# IDX_CTRL.net
KiCad netlist of a schematic drawn in Altium Designer
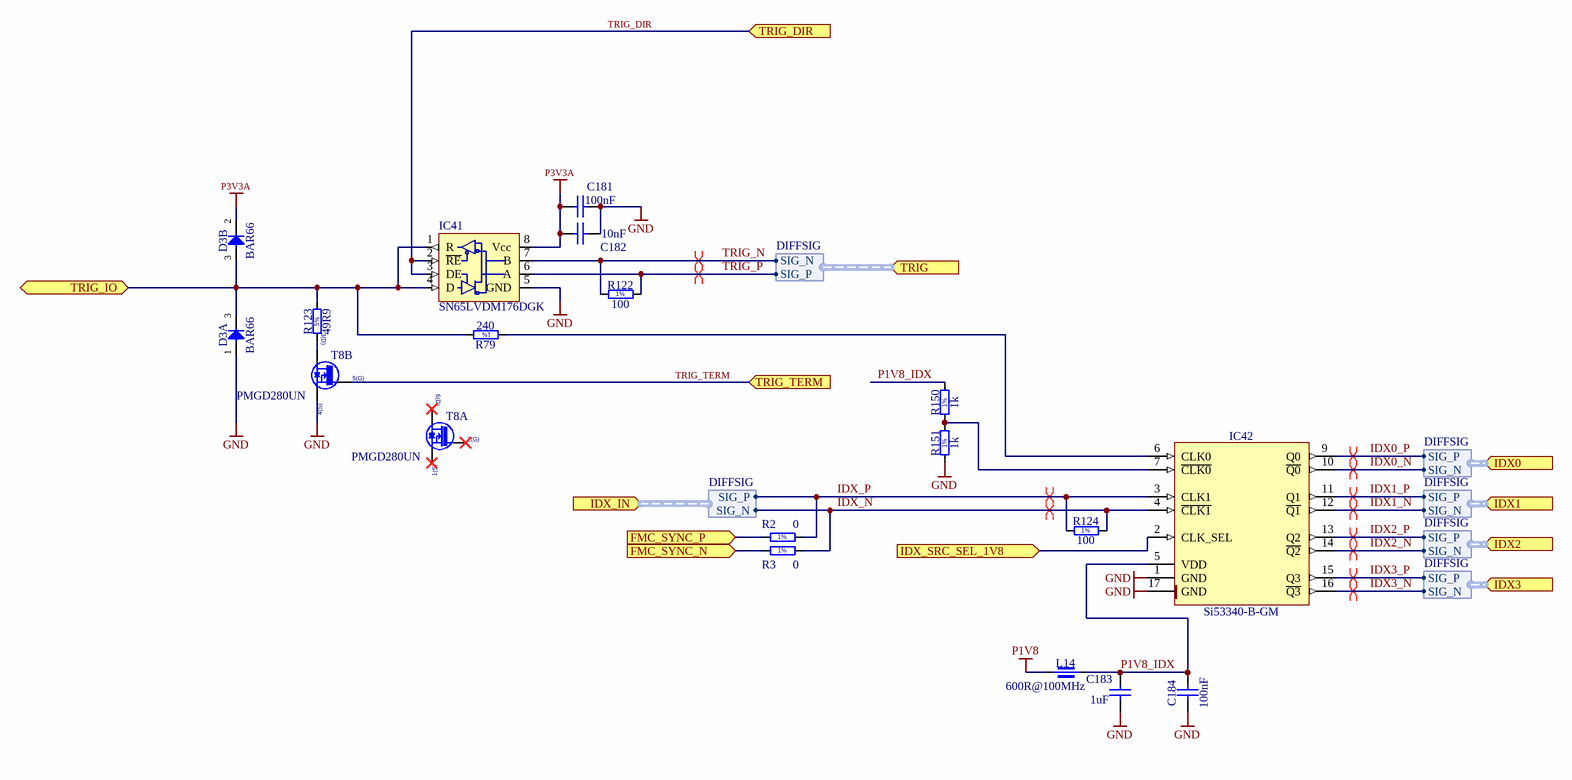
[diagram p0: IDX_CTRL.SchDoc]

(export (version "E")
  (design (tool "Eeschema 10.0.6"))
  (components
    (comp (ref "C181")
      (value "100nF")
      (footprint "CAPC0603X33N")
      (description "Non-polarised capacitor")
      (fields
        (field (name "PART NUMBER") "CC0201_100NF_6.3V_10%_X5R")
        (field (name "VOLTAGE") "6.3V")
        (field (name "AUTHOR") "CERN DEM JLC")
      )
      (libsource (lib "Capacitors") (part "Capacitor - non polarized"))
    )
    (comp (ref "C182")
      (value "10nF")
      (footprint "CAPC0603X33N")
      (description "Non-polarised capacitor")
      (fields
        (field (name "PART NUMBER") "CC0201_10NF_10V_10%_X5R")
        (field (name "VOLTAGE") "10V")
        (field (name "AUTHOR") "CERN DEM JLC")
      )
      (libsource (lib "Capacitors") (part "Capacitor - non polarized"))
    )
    (comp (ref "C183")
      (value "1uF")
      (footprint "CAPC1005X55N")
      (description "Non-polarised capacitor")
      (fields
        (field (name "PART NUMBER") "CC0402_1UF_16V_10%_X5R")
        (field (name "VOLTAGE") "16V")
        (field (name "AUTHOR") "CERN DEM JLC")
      )
      (libsource (lib "Capacitors") (part "Capacitor - non polarized"))
    )
    (comp (ref "C184")
      (value "100nF")
      (footprint "CAPC0603X33N")
      (description "Non-polarised capacitor")
      (fields
        (field (name "PART NUMBER") "CC0201_100NF_6.3V_10%_X5R")
        (field (name "VOLTAGE") "6.3V")
        (field (name "AUTHOR") "CERN DEM JLC")
      )
      (libsource (lib "Capacitors") (part "Capacitor - non polarized"))
    )
    (comp (ref "D3")
      (value "BAR66")
      (footprint "SOT95P240X110-3N")
      (description "Serial Diode")
      (fields
        (field (name "VOLTAGE") "150V")
        (field (name "POWER") "250mA")
        (field (name "AUTHOR") "CERN DEM JLC")
      )
      (libsource (lib "ICs And Semiconductors") (part "Diode x2 A1C3_A3C2"))
    )
    (comp (ref "IC41")
      (value "SN65LVDM176DGK")
      (footprint "MSOP8 TI/AD")
      (description "High Speed Differential Transceiver LVDS/LVTTL")
      (libsource (lib "Buffers & Drivers") (part "SN65LVDM176"))
    )
    (comp (ref "IC42")
      (value "Si53340-B-GM")
      (footprint "QFN50P300X300X90-17N-S175")
      (description "Low-Jitter LVDS Fanout Clock Buffers, 10-Output,  Any-Input, Any-Frequency up to 1250MHz")
      (fields (field (name "MANUFACTURER") "SILICON LABS") (field (name "AUTHOR") "CERN DEM MR"))
      (libsource (lib "ICs And Semiconductors") (part "Si53340"))
    )
    (comp (ref "L14")
      (value "600R@100MHz")
      (footprint "INDC1005X55N")
      (fields
        (field (name "PART NUMBER") "IND0402_MURATA_BLM15HD601SN1")
        (field (name "POWER") "300mA")
        (field (name "TOLERANCE") "±25%")
        (field (name "AUTHOR") "CERN DEM JLC")
      )
      (libsource (lib "Inductors & Transformers") (part "Ferrite Bead"))
    )
    (comp (ref "R2")
      (value "0")
      (footprint "RESC1005X40N")
      (description "Resistor - 1%")
      (fields
        (field (name "PART NUMBER") "R0402_0R_JUMPER")
        (field (name "MANUFACTURER") "GENERIC")
        (field (name "AUTHOR") "CERN DEM JLC")
      )
      (libsource (lib "Resistors") (part "Resistor - 1%"))
    )
    (comp (ref "R3")
      (value "0")
      (footprint "RESC1005X40N")
      (description "Resistor - 1%")
      (fields
        (field (name "PART NUMBER") "R0402_0R_JUMPER")
        (field (name "MANUFACTURER") "GENERIC")
        (field (name "AUTHOR") "CERN DEM JLC")
      )
      (libsource (lib "Resistors") (part "Resistor - 1%"))
    )
    (comp (ref "R79")
      (value "240")
      (footprint "RESC1005X40N")
      (description "Resistor - 1%")
      (fields
        (field (name "PART NUMBER") "R0402_240R_1%_0.0625W_100PPM")
        (field (name "POWER") "0.0625W")
        (field (name "AUTHOR") "CERN DEM JLC")
      )
      (libsource (lib "Resistors") (part "Resistor - 1%"))
    )
    (comp (ref "R122")
      (value "100")
      (footprint "RESC0603X28N")
      (description "Resistor - 1%")
      (fields
        (field (name "PART NUMBER") "R0201_100R_1%_0.05W_200PPM")
        (field (name "POWER") "0.05W")
        (field (name "AUTHOR") "CERN DEM JLC")
      )
      (libsource (lib "Resistors") (part "Resistor - 1%"))
    )
    (comp (ref "R123")
      (value "49R9")
      (footprint "RESC3225X70N")
      (description "Resistor - 5%")
      (fields
        (field (name "PART NUMBER") "R1210_49R9_1%_0.33W_100PPM")
        (field (name "POWER") "0.33W")
        (field (name "AUTHOR") "CERN DEM JLC")
      )
      (libsource (lib "Resistors") (part "Resistor - 5%"))
    )
    (comp (ref "R124")
      (value "100")
      (footprint "RESC0603X28N")
      (description "Resistor - 1%")
      (fields
        (field (name "PART NUMBER") "R0201_100R_1%_0.05W_200PPM")
        (field (name "POWER") "0.05W")
        (field (name "AUTHOR") "CERN DEM JLC")
      )
      (libsource (lib "Resistors") (part "Resistor - 1%"))
    )
    (comp (ref "R150")
      (value "1k")
      (footprint "RESC1005X40N")
      (description "Resistor - 1%")
      (fields
        (field (name "TOLERANCE") "±1%")
        (field (name "POWER") "0.0625W")
        (field (name "AUTHOR") "CERN DEM JLC")
      )
      (libsource (lib "Resistors") (part "Resistor - 1%"))
    )
    (comp (ref "R151")
      (value "1k")
      (footprint "RESC1005X40N")
      (description "Resistor - 1%")
      (fields
        (field (name "TOLERANCE") "±1%")
        (field (name "POWER") "0.0625W")
        (field (name "AUTHOR") "CERN DEM JLC")
      )
      (libsource (lib "Resistors") (part "Resistor - 1%"))
    )
    (comp (ref "T8")
      (value "PMGD280UN")
      (footprint "SOT65P210X110-6N")
      (description "Dual N-Channel micro TrenchMOS™ Ultra Low Level FET")
      (fields (field (name "MANUFACTURER") "NXP SEMICONDUCTORS") (field (name "AUTHOR") "CERN DEM JLC"))
      (libsource (lib "ICs And Semiconductors") (part "PMGD280UN"))
    )
  )
  (nets
    (net (code "2") (name "/FMC_SYNC_N") (class "Default")
      (node (ref "R3") (pin "1") (pinfunction "1_1") (pintype "passive"))
    )
    (net (code "3") (name "/FMC_SYNC_P") (class "Default")
      (node (ref "R2") (pin "1") (pinfunction "1_1") (pintype "passive"))
    )
    (net (code "4") (name "/IDX0_N") (class "Default")
      (node (ref "IC42") (pin "10") (pinfunction "~{Q0}_10") (pintype "output"))
    )
    (net (code "5") (name "/IDX0_P") (class "Default")
      (node (ref "IC42") (pin "9") (pinfunction "Q0_9") (pintype "output"))
    )
    (net (code "6") (name "/IDX1_N") (class "Default")
      (node (ref "IC42") (pin "12") (pinfunction "~{Q1}_12") (pintype "output"))
    )
    (net (code "7") (name "/IDX1_P") (class "Default")
      (node (ref "IC42") (pin "11") (pinfunction "Q1_11") (pintype "output"))
    )
    (net (code "8") (name "/IDX2_N") (class "Default")
      (node (ref "IC42") (pin "14") (pinfunction "~{Q2}_14") (pintype "output"))
    )
    (net (code "9") (name "/IDX2_P") (class "Default")
      (node (ref "IC42") (pin "13") (pinfunction "Q2_13") (pintype "output"))
    )
    (net (code "10") (name "/IDX3_N") (class "Default")
      (node (ref "IC42") (pin "16") (pinfunction "~{Q3}_16") (pintype "output"))
    )
    (net (code "11") (name "/IDX3_P") (class "Default")
      (node (ref "IC42") (pin "15") (pinfunction "Q3_15") (pintype "output"))
    )
    (net (code "12") (name "/IDX_N") (class "Default")
      (node (ref "IC42") (pin "4") (pinfunction "~{CLK1}_4") (pintype "input"))
      (node (ref "R124") (pin "2") (pinfunction "2_2") (pintype "passive"))
      (node (ref "R3") (pin "2") (pinfunction "2_2") (pintype "passive"))
    )
    (net (code "13") (name "/IDX_P") (class "Default")
      (node (ref "IC42") (pin "3") (pinfunction "CLK1_3") (pintype "input"))
      (node (ref "R124") (pin "1") (pinfunction "1_1") (pintype "passive"))
      (node (ref "R2") (pin "2") (pinfunction "2_2") (pintype "passive"))
    )
    (net (code "14") (name "/IDX_SRC_SEL_1V8") (class "Default")
      (node (ref "IC42") (pin "2") (pinfunction "CLK_SEL_2") (pintype "input"))
    )
    (net (code "15") (name "/P1V8_IDX") (class "Default")
      (node (ref "C183") (pin "2") (pinfunction "2_2") (pintype "passive"))
      (node (ref "C184") (pin "2") (pinfunction "2_2") (pintype "passive"))
      (node (ref "IC42") (pin "5") (pinfunction "VDD_5") (pintype "power_in"))
      (node (ref "L14") (pin "2") (pinfunction "2_2") (pintype "passive"))
      (node (ref "R150") (pin "2") (pinfunction "2_2") (pintype "passive"))
    )
    (net (code "16") (name "/TRIG_DIR") (class "Default")
      (node (ref "IC41") (pin "2") (pinfunction "~{RE}_2") (pintype "input"))
      (node (ref "IC41") (pin "3") (pinfunction "DE_3") (pintype "input"))
    )
    (net (code "17") (name "/TRIG_IO") (class "Default")
      (node (ref "D3") (pin "3") (pinfunction "COMAC_3") (pintype "passive"))
      (node (ref "IC41") (pin "1") (pinfunction "R_1") (pintype "output"))
      (node (ref "IC41") (pin "4") (pinfunction "D_4") (pintype "input"))
      (node (ref "R123") (pin "2") (pinfunction "2_2") (pintype "passive"))
      (node (ref "R79") (pin "2") (pinfunction "2_2") (pintype "passive"))
    )
    (net (code "18") (name "/TRIG_N") (class "Default")
      (node (ref "IC41") (pin "7") (pinfunction "B_7") (pintype "bidirectional"))
      (node (ref "R122") (pin "1") (pinfunction "1_1") (pintype "passive"))
    )
    (net (code "19") (name "/TRIG_P") (class "Default")
      (node (ref "IC41") (pin "6") (pinfunction "A_6") (pintype "bidirectional"))
      (node (ref "R122") (pin "2") (pinfunction "2_2") (pintype "passive"))
    )
    (net (code "20") (name "/TRIG_TERM") (class "Default")
      (node (ref "T8") (pin "5") (pinfunction "G_5") (pintype "passive"))
    )
    (net (code "22") (name "GND") (class "Default")
      (node (ref "C181") (pin "2") (pinfunction "2_2") (pintype "passive"))
      (node (ref "C182") (pin "2") (pinfunction "2_2") (pintype "passive"))
      (node (ref "C183") (pin "1") (pinfunction "1_1") (pintype "passive"))
      (node (ref "C184") (pin "1") (pinfunction "1_1") (pintype "passive"))
      (node (ref "D3") (pin "1") (pinfunction "A_1") (pintype "passive"))
      (node (ref "IC41") (pin "5") (pinfunction "GND_5") (pintype "power_in"))
      (node (ref "IC42") (pin "1") (pinfunction "GND_1") (pintype "power_in"))
      (node (ref "IC42") (pin "17") (pinfunction "GND_17") (pintype "power_in"))
      (node (ref "R151") (pin "1") (pinfunction "1_1") (pintype "passive"))
      (node (ref "T8") (pin "4") (pinfunction "S_4") (pintype "passive"))
    )
    (net (code "23") (name "Net-(IC42-CLK0)") (class "Default")
      (node (ref "IC42") (pin "6") (pinfunction "CLK0_6") (pintype "input"))
      (node (ref "R79") (pin "1") (pinfunction "1_1") (pintype "passive"))
    )
    (net (code "24") (name "Net-(IC42-~{CLK0})") (class "Default")
      (node (ref "IC42") (pin "7") (pinfunction "~{CLK0}_7") (pintype "input"))
      (node (ref "R150") (pin "1") (pinfunction "1_1") (pintype "passive"))
      (node (ref "R151") (pin "2") (pinfunction "2_2") (pintype "passive"))
    )
    (net (code "25") (name "Net-(T8B-D)") (class "Default")
      (node (ref "R123") (pin "1") (pinfunction "1_1") (pintype "passive"))
      (node (ref "T8") (pin "3") (pinfunction "D_3") (pintype "passive"))
    )
    (net (code "26") (name "P1V8") (class "Default")
      (node (ref "L14") (pin "1") (pinfunction "1_1") (pintype "passive"))
    )
    (net (code "27") (name "P3V3A") (class "Default")
      (node (ref "C181") (pin "1") (pinfunction "1_1") (pintype "passive"))
      (node (ref "C182") (pin "1") (pinfunction "1_1") (pintype "passive"))
      (node (ref "D3") (pin "2") (pinfunction "C_2") (pintype "passive"))
      (node (ref "IC41") (pin "8") (pinfunction "Vcc_8") (pintype "power_in"))
    )
    (net (code "28") (name "unconnected-(T8A-D-Pad6)") (class "Default")
      (node (ref "T8") (pin "6") (pinfunction "D_6") (pintype "passive+no_connect"))
    )
    (net (code "29") (name "unconnected-(T8A-G-Pad2)") (class "Default")
      (node (ref "T8") (pin "2") (pinfunction "G_2") (pintype "passive+no_connect"))
    )
    (net (code "30") (name "unconnected-(T8A-S-Pad1)") (class "Default")
      (node (ref "T8") (pin "1") (pinfunction "S_1") (pintype "passive+no_connect"))
    )
  )
)
